# axiom_beta_plugin_module_1xPMOD.net
KiCad netlist of a schematic drawn in EAGLE
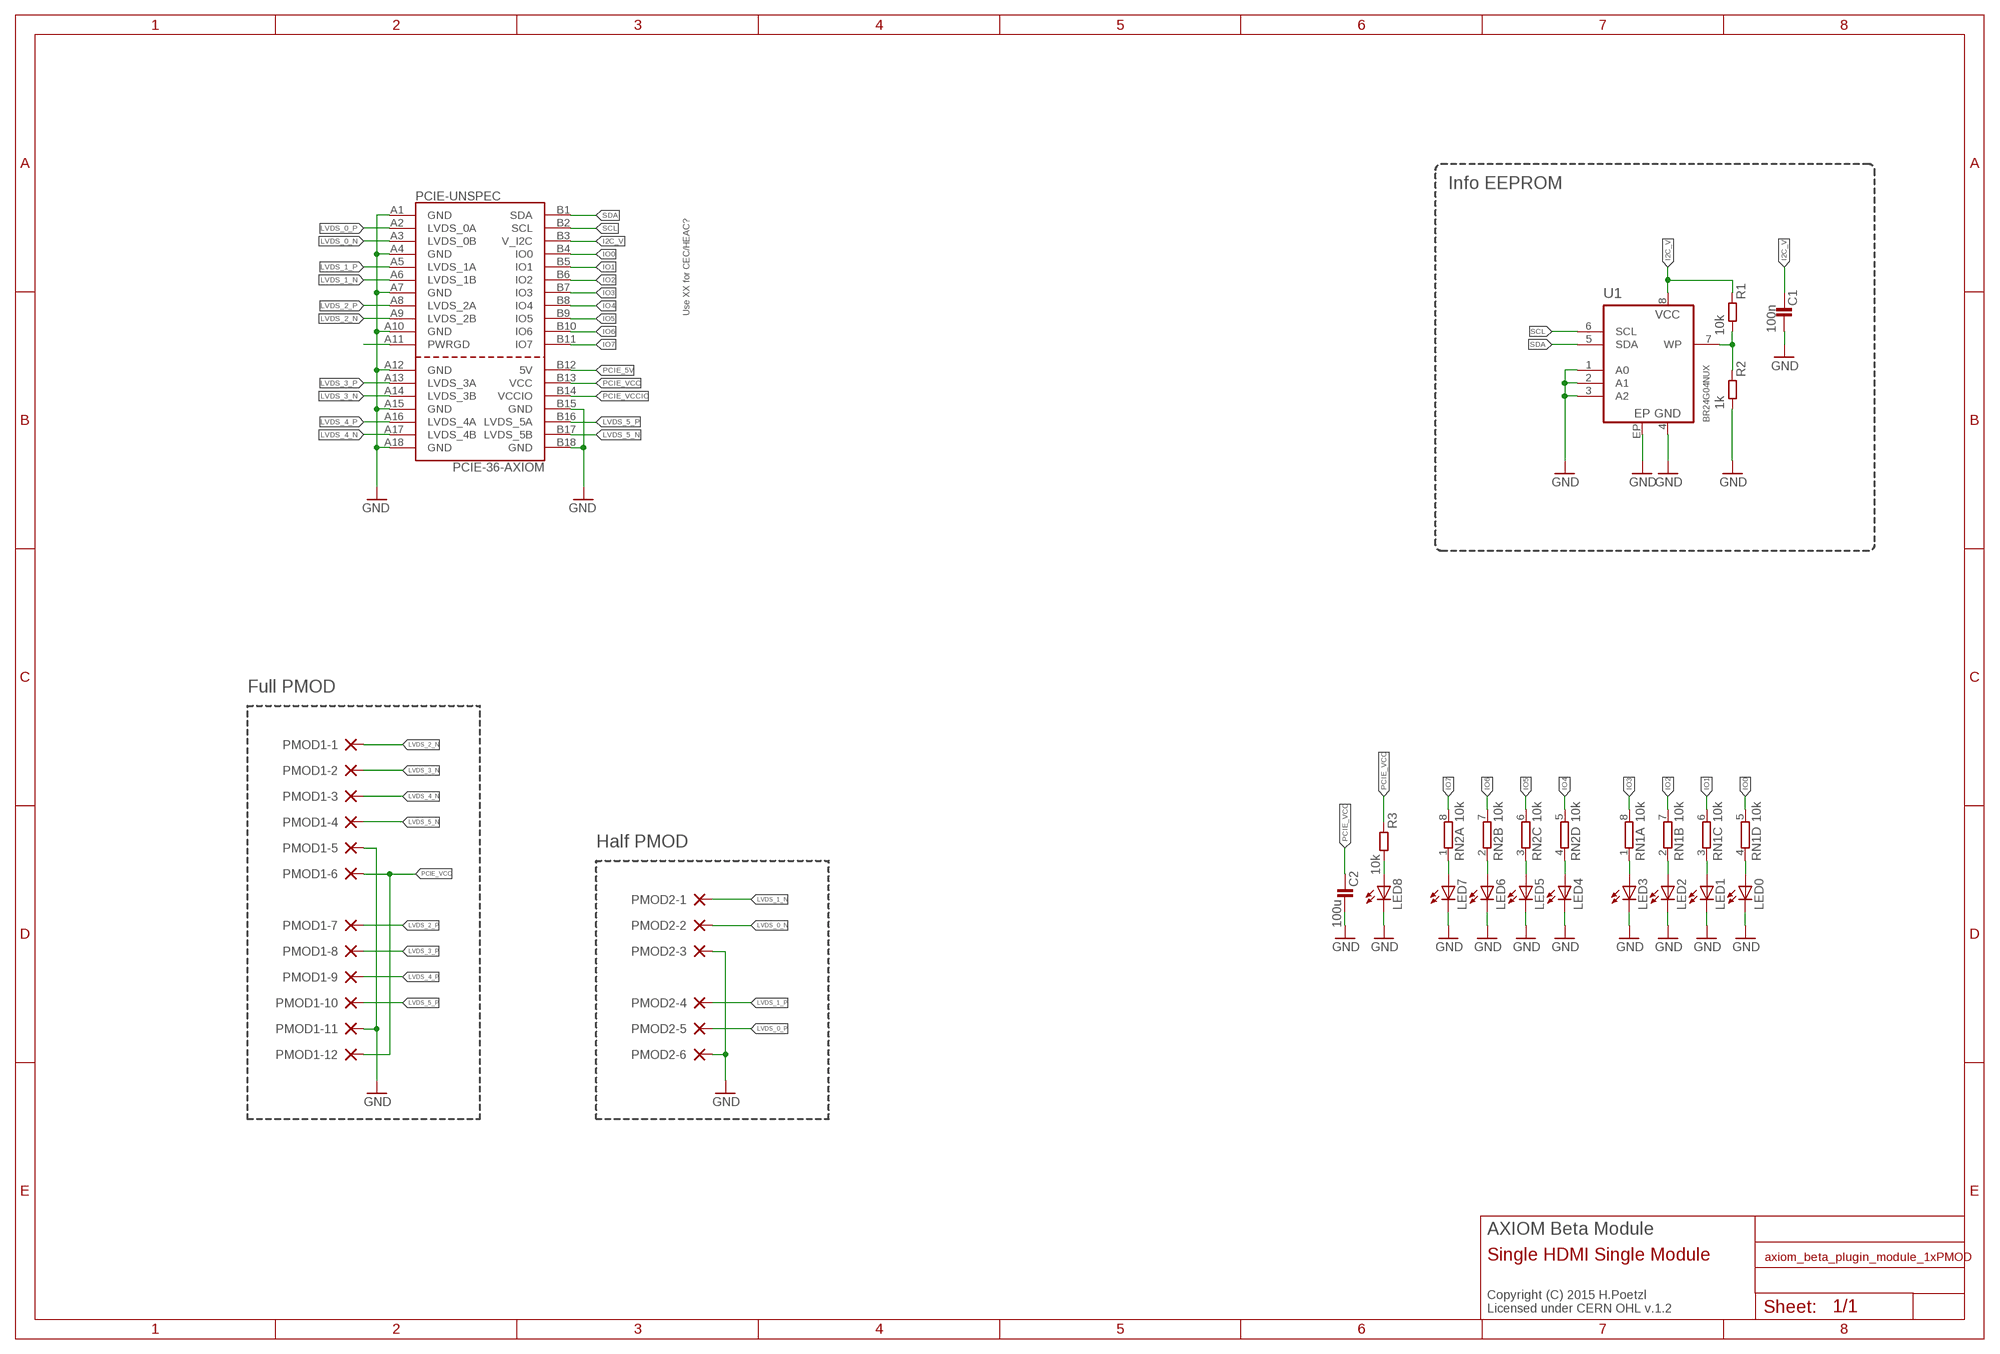
[diagram p0: schematic, sheet 1]

(export (version "E")
  (design (tool "Eeschema 10.0.6"))
  (components
    (comp (ref "C1")
      (value "100n")
      (footprint "eagle-import:0402-B")
      (libsource (lib "eagle-import") (part "C0402-B"))
    )
    (comp (ref "C2")
      (value "100u")
      (footprint "eagle-import:1206-A")
      (libsource (lib "eagle-import") (part "C1206-A"))
    )
    (comp (ref "LED0")
      (value "LEDCHIPLED_0603")
      (footprint "eagle-import:CHIPLED_0603")
      (libsource (lib "eagle-import") (part "LEDCHIPLED_0603"))
    )
    (comp (ref "LED1")
      (value "LEDCHIPLED_0603")
      (footprint "eagle-import:CHIPLED_0603")
      (libsource (lib "eagle-import") (part "LEDCHIPLED_0603"))
    )
    (comp (ref "LED2")
      (value "LEDCHIPLED_0603")
      (footprint "eagle-import:CHIPLED_0603")
      (libsource (lib "eagle-import") (part "LEDCHIPLED_0603"))
    )
    (comp (ref "LED3")
      (value "LEDCHIPLED_0603")
      (footprint "eagle-import:CHIPLED_0603")
      (libsource (lib "eagle-import") (part "LEDCHIPLED_0603"))
    )
    (comp (ref "LED4")
      (value "LEDCHIPLED_0603")
      (footprint "eagle-import:CHIPLED_0603")
      (libsource (lib "eagle-import") (part "LEDCHIPLED_0603"))
    )
    (comp (ref "LED5")
      (value "LEDCHIPLED_0603")
      (footprint "eagle-import:CHIPLED_0603")
      (libsource (lib "eagle-import") (part "LEDCHIPLED_0603"))
    )
    (comp (ref "LED6")
      (value "LEDCHIPLED_0603")
      (footprint "eagle-import:CHIPLED_0603")
      (libsource (lib "eagle-import") (part "LEDCHIPLED_0603"))
    )
    (comp (ref "LED7")
      (value "LEDCHIPLED_0603")
      (footprint "eagle-import:CHIPLED_0603")
      (libsource (lib "eagle-import") (part "LEDCHIPLED_0603"))
    )
    (comp (ref "LED8")
      (value "LEDCHIPLED_0603")
      (footprint "eagle-import:CHIPLED_0603")
      (libsource (lib "eagle-import") (part "LEDCHIPLED_0603"))
    )
    (comp (ref "PCIE-UNSPEC")
      (value "PCIE-36-AXIOM")
      (footprint "eagle-import:PCIE-36-AXIOM")
      (libsource (lib "eagle-import") (part "PCIE-36-AXIOM"))
    )
    (comp (ref "PMOD1-1")
      (value "SMD-PAD1.6X3.8MM-U")
      (footprint "eagle-import:1.6X3.8U-MM")
      (libsource (lib "eagle-import") (part "SMD-PAD1.6X3.8MM-U"))
    )
    (comp (ref "PMOD1-2")
      (value "SMD-PAD1.6X3.8MM-U")
      (footprint "eagle-import:1.6X3.8U-MM")
      (libsource (lib "eagle-import") (part "SMD-PAD1.6X3.8MM-U"))
    )
    (comp (ref "PMOD1-3")
      (value "SMD-PAD1.6X3.8MM-U")
      (footprint "eagle-import:1.6X3.8U-MM")
      (libsource (lib "eagle-import") (part "SMD-PAD1.6X3.8MM-U"))
    )
    (comp (ref "PMOD1-4")
      (value "SMD-PAD1.6X3.8MM-U")
      (footprint "eagle-import:1.6X3.8U-MM")
      (libsource (lib "eagle-import") (part "SMD-PAD1.6X3.8MM-U"))
    )
    (comp (ref "PMOD1-5")
      (value "SMD-PAD1.6X3.8MM-U")
      (footprint "eagle-import:1.6X3.8U-MM")
      (libsource (lib "eagle-import") (part "SMD-PAD1.6X3.8MM-U"))
    )
    (comp (ref "PMOD1-6")
      (value "SMD-PAD1.6X3.8MM-U")
      (footprint "eagle-import:1.6X3.8U-MM")
      (libsource (lib "eagle-import") (part "SMD-PAD1.6X3.8MM-U"))
    )
    (comp (ref "PMOD1-7")
      (value "SMD-PAD1.6X3.8MM-U")
      (footprint "eagle-import:1.6X3.8U-MM")
      (libsource (lib "eagle-import") (part "SMD-PAD1.6X3.8MM-U"))
    )
    (comp (ref "PMOD1-8")
      (value "SMD-PAD1.6X3.8MM-U")
      (footprint "eagle-import:1.6X3.8U-MM")
      (libsource (lib "eagle-import") (part "SMD-PAD1.6X3.8MM-U"))
    )
    (comp (ref "PMOD1-9")
      (value "SMD-PAD1.6X3.8MM-U")
      (footprint "eagle-import:1.6X3.8U-MM")
      (libsource (lib "eagle-import") (part "SMD-PAD1.6X3.8MM-U"))
    )
    (comp (ref "PMOD1-10")
      (value "SMD-PAD1.6X3.8MM-U")
      (footprint "eagle-import:1.6X3.8U-MM")
      (libsource (lib "eagle-import") (part "SMD-PAD1.6X3.8MM-U"))
    )
    (comp (ref "PMOD1-11")
      (value "SMD-PAD1.6X3.8MM-U")
      (footprint "eagle-import:1.6X3.8U-MM")
      (libsource (lib "eagle-import") (part "SMD-PAD1.6X3.8MM-U"))
    )
    (comp (ref "PMOD1-12")
      (value "SMD-PAD1.6X3.8MM-U")
      (footprint "eagle-import:1.6X3.8U-MM")
      (libsource (lib "eagle-import") (part "SMD-PAD1.6X3.8MM-U"))
    )
    (comp (ref "PMOD2-1")
      (value "SMD-PAD1.6X3.8MM-U")
      (footprint "eagle-import:1.6X3.8U-MM")
      (libsource (lib "eagle-import") (part "SMD-PAD1.6X3.8MM-U"))
    )
    (comp (ref "PMOD2-2")
      (value "SMD-PAD1.6X3.8MM-U")
      (footprint "eagle-import:1.6X3.8U-MM")
      (libsource (lib "eagle-import") (part "SMD-PAD1.6X3.8MM-U"))
    )
    (comp (ref "PMOD2-3")
      (value "SMD-PAD1.6X3.8MM-U")
      (footprint "eagle-import:1.6X3.8U-MM")
      (libsource (lib "eagle-import") (part "SMD-PAD1.6X3.8MM-U"))
    )
    (comp (ref "PMOD2-4")
      (value "SMD-PAD1.6X3.8MM-U")
      (footprint "eagle-import:1.6X3.8U-MM")
      (libsource (lib "eagle-import") (part "SMD-PAD1.6X3.8MM-U"))
    )
    (comp (ref "PMOD2-5")
      (value "SMD-PAD1.6X3.8MM-U")
      (footprint "eagle-import:1.6X3.8U-MM")
      (libsource (lib "eagle-import") (part "SMD-PAD1.6X3.8MM-U"))
    )
    (comp (ref "PMOD2-6")
      (value "SMD-PAD1.6X3.8MM-U")
      (footprint "eagle-import:1.6X3.8U-MM")
      (libsource (lib "eagle-import") (part "SMD-PAD1.6X3.8MM-U"))
    )
    (comp (ref "R1")
      (value "10k")
      (footprint "eagle-import:0402-B")
      (libsource (lib "eagle-import") (part "R0402-B"))
    )
    (comp (ref "R2")
      (value "1k")
      (footprint "eagle-import:0402-B")
      (libsource (lib "eagle-import") (part "R0402-B"))
    )
    (comp (ref "R3")
      (value "10k")
      (footprint "eagle-import:0402-B")
      (libsource (lib "eagle-import") (part "R0402-B"))
    )
    (comp (ref "RN1")
      (value "10k")
      (footprint "eagle-import:CAY16")
      (libsource (lib "eagle-import") (part "4R-NCAY16"))
    )
    (comp (ref "RN2")
      (value "10k")
      (footprint "eagle-import:CAY16")
      (libsource (lib "eagle-import") (part "4R-NCAY16"))
    )
    (comp (ref "U1")
      (value "BR24G04NUX")
      (footprint "eagle-import:DFN200X300X100-9N")
      (libsource (lib "eagle-import") (part "BR24G04NUX"))
    )
  )
  (nets
    (net (code "1") (name "GND") (class "Default")
      (node (ref "C1") (pin "2") (pinfunction "2_2") (pintype "passive"))
      (node (ref "C2") (pin "2") (pinfunction "2_2") (pintype "passive"))
      (node (ref "LED0") (pin "C") (pinfunction "C_C") (pintype "passive"))
      (node (ref "LED1") (pin "C") (pinfunction "C_C") (pintype "passive"))
      (node (ref "LED2") (pin "C") (pinfunction "C_C") (pintype "passive"))
      (node (ref "LED3") (pin "C") (pinfunction "C_C") (pintype "passive"))
      (node (ref "LED4") (pin "C") (pinfunction "C_C") (pintype "passive"))
      (node (ref "LED5") (pin "C") (pinfunction "C_C") (pintype "passive"))
      (node (ref "LED6") (pin "C") (pinfunction "C_C") (pintype "passive"))
      (node (ref "LED7") (pin "C") (pinfunction "C_C") (pintype "passive"))
      (node (ref "LED8") (pin "C") (pinfunction "C_C") (pintype "passive"))
      (node (ref "PCIE-UNSPEC") (pin "A1") (pinfunction "GND_A1") (pintype "passive"))
      (node (ref "PCIE-UNSPEC") (pin "A10") (pinfunction "GND_A10") (pintype "passive"))
      (node (ref "PCIE-UNSPEC") (pin "A12") (pinfunction "GND_A12") (pintype "passive"))
      (node (ref "PCIE-UNSPEC") (pin "A15") (pinfunction "GND_A15") (pintype "passive"))
      (node (ref "PCIE-UNSPEC") (pin "A18") (pinfunction "GND_A18") (pintype "passive"))
      (node (ref "PCIE-UNSPEC") (pin "A4") (pinfunction "GND_A4") (pintype "passive"))
      (node (ref "PCIE-UNSPEC") (pin "A7") (pinfunction "GND_A7") (pintype "passive"))
      (node (ref "PCIE-UNSPEC") (pin "B15") (pinfunction "GND_B15") (pintype "passive"))
      (node (ref "PCIE-UNSPEC") (pin "B18") (pinfunction "GND_B18") (pintype "passive"))
      (node (ref "PMOD1-11") (pin "1") (pinfunction "P_1") (pintype "passive"))
      (node (ref "PMOD1-5") (pin "1") (pinfunction "P_1") (pintype "passive"))
      (node (ref "PMOD2-3") (pin "1") (pinfunction "P_1") (pintype "passive"))
      (node (ref "PMOD2-6") (pin "1") (pinfunction "P_1") (pintype "passive"))
      (node (ref "R2") (pin "2") (pinfunction "2_2") (pintype "passive"))
      (node (ref "U1") (pin "1") (pinfunction "A0_1") (pintype "input"))
      (node (ref "U1") (pin "2") (pinfunction "A1_2") (pintype "input"))
      (node (ref "U1") (pin "3") (pinfunction "A2_3") (pintype "input"))
      (node (ref "U1") (pin "4") (pinfunction "GND_4") (pintype "passive"))
      (node (ref "U1") (pin "EP") (pinfunction "EP_EP") (pintype "passive"))
    )
    (net (code "2") (name "I2C_V") (class "Default")
      (node (ref "C1") (pin "1") (pinfunction "1_1") (pintype "passive"))
      (node (ref "PCIE-UNSPEC") (pin "B3") (pinfunction "V_I2C_B3") (pintype "passive"))
      (node (ref "R1") (pin "1") (pinfunction "1_1") (pintype "passive"))
      (node (ref "U1") (pin "8") (pinfunction "VCC_8") (pintype "power_in"))
    )
    (net (code "3") (name "IO0") (class "Default")
      (node (ref "PCIE-UNSPEC") (pin "B4") (pinfunction "IO0_B4") (pintype "passive"))
      (node (ref "RN1") (pin "5") (pinfunction "2_5") (pintype "passive"))
    )
    (net (code "4") (name "IO1") (class "Default")
      (node (ref "PCIE-UNSPEC") (pin "B5") (pinfunction "IO1_B5") (pintype "passive"))
      (node (ref "RN1") (pin "6") (pinfunction "2_6") (pintype "passive"))
    )
    (net (code "5") (name "IO2") (class "Default")
      (node (ref "PCIE-UNSPEC") (pin "B6") (pinfunction "IO2_B6") (pintype "passive"))
      (node (ref "RN1") (pin "7") (pinfunction "2_7") (pintype "passive"))
    )
    (net (code "6") (name "IO3") (class "Default")
      (node (ref "PCIE-UNSPEC") (pin "B7") (pinfunction "IO3_B7") (pintype "passive"))
      (node (ref "RN1") (pin "8") (pinfunction "2_8") (pintype "passive"))
    )
    (net (code "7") (name "IO4") (class "Default")
      (node (ref "PCIE-UNSPEC") (pin "B8") (pinfunction "IO4_B8") (pintype "passive"))
      (node (ref "RN2") (pin "5") (pinfunction "2_5") (pintype "passive"))
    )
    (net (code "8") (name "IO5") (class "Default")
      (node (ref "PCIE-UNSPEC") (pin "B9") (pinfunction "IO5_B9") (pintype "passive"))
      (node (ref "RN2") (pin "6") (pinfunction "2_6") (pintype "passive"))
    )
    (net (code "9") (name "IO6") (class "Default")
      (node (ref "PCIE-UNSPEC") (pin "B10") (pinfunction "IO6_B10") (pintype "passive"))
      (node (ref "RN2") (pin "7") (pinfunction "2_7") (pintype "passive"))
    )
    (net (code "10") (name "IO7") (class "Default")
      (node (ref "PCIE-UNSPEC") (pin "B11") (pinfunction "IO7_B11") (pintype "passive"))
      (node (ref "RN2") (pin "8") (pinfunction "2_8") (pintype "passive"))
    )
    (net (code "11") (name "LVDS_0_N") (class "Default")
      (node (ref "PCIE-UNSPEC") (pin "A3") (pinfunction "LVDS_0B_A3") (pintype "passive"))
      (node (ref "PMOD2-2") (pin "1") (pinfunction "P_1") (pintype "passive"))
    )
    (net (code "12") (name "LVDS_0_P") (class "Default")
      (node (ref "PCIE-UNSPEC") (pin "A2") (pinfunction "LVDS_0A_A2") (pintype "passive"))
      (node (ref "PMOD2-5") (pin "1") (pinfunction "P_1") (pintype "passive"))
    )
    (net (code "13") (name "LVDS_1_N") (class "Default")
      (node (ref "PCIE-UNSPEC") (pin "A6") (pinfunction "LVDS_1B_A6") (pintype "passive"))
      (node (ref "PMOD2-1") (pin "1") (pinfunction "P_1") (pintype "passive"))
    )
    (net (code "14") (name "LVDS_1_P") (class "Default")
      (node (ref "PCIE-UNSPEC") (pin "A5") (pinfunction "LVDS_1A_A5") (pintype "passive"))
      (node (ref "PMOD2-4") (pin "1") (pinfunction "P_1") (pintype "passive"))
    )
    (net (code "15") (name "LVDS_2_N") (class "Default")
      (node (ref "PCIE-UNSPEC") (pin "A9") (pinfunction "LVDS_2B_A9") (pintype "passive"))
      (node (ref "PMOD1-1") (pin "1") (pinfunction "P_1") (pintype "passive"))
    )
    (net (code "16") (name "LVDS_2_P") (class "Default")
      (node (ref "PCIE-UNSPEC") (pin "A8") (pinfunction "LVDS_2A_A8") (pintype "passive"))
      (node (ref "PMOD1-7") (pin "1") (pinfunction "P_1") (pintype "passive"))
    )
    (net (code "17") (name "LVDS_3_N") (class "Default")
      (node (ref "PCIE-UNSPEC") (pin "A14") (pinfunction "LVDS_3B_A14") (pintype "passive"))
      (node (ref "PMOD1-2") (pin "1") (pinfunction "P_1") (pintype "passive"))
    )
    (net (code "18") (name "LVDS_3_P") (class "Default")
      (node (ref "PCIE-UNSPEC") (pin "A13") (pinfunction "LVDS_3A_A13") (pintype "passive"))
      (node (ref "PMOD1-8") (pin "1") (pinfunction "P_1") (pintype "passive"))
    )
    (net (code "19") (name "LVDS_4_N") (class "Default")
      (node (ref "PCIE-UNSPEC") (pin "A17") (pinfunction "LVDS_4B_A17") (pintype "passive"))
      (node (ref "PMOD1-3") (pin "1") (pinfunction "P_1") (pintype "passive"))
    )
    (net (code "20") (name "LVDS_4_P") (class "Default")
      (node (ref "PCIE-UNSPEC") (pin "A16") (pinfunction "LVDS_4A_A16") (pintype "passive"))
      (node (ref "PMOD1-9") (pin "1") (pinfunction "P_1") (pintype "passive"))
    )
    (net (code "21") (name "LVDS_5_N") (class "Default")
      (node (ref "PCIE-UNSPEC") (pin "B17") (pinfunction "LVDS_5B_B17") (pintype "passive"))
      (node (ref "PMOD1-4") (pin "1") (pinfunction "P_1") (pintype "passive"))
    )
    (net (code "22") (name "LVDS_5_P") (class "Default")
      (node (ref "PCIE-UNSPEC") (pin "B16") (pinfunction "LVDS_5A_B16") (pintype "passive"))
      (node (ref "PMOD1-10") (pin "1") (pinfunction "P_1") (pintype "passive"))
    )
    (net (code "23") (name "Net-(LED3-PadA)") (class "Default")
      (node (ref "LED3") (pin "A") (pinfunction "A_A") (pintype "passive"))
      (node (ref "RN1") (pin "1") (pinfunction "1_1") (pintype "passive"))
    )
    (net (code "24") (name "Net-(LED7-PadA)") (class "Default")
      (node (ref "LED7") (pin "A") (pinfunction "A_A") (pintype "passive"))
      (node (ref "RN2") (pin "1") (pinfunction "1_1") (pintype "passive"))
    )
    (net (code "25") (name "Net-(LED8-PadA)") (class "Default")
      (node (ref "LED8") (pin "A") (pinfunction "A_A") (pintype "passive"))
      (node (ref "R3") (pin "2") (pinfunction "2_2") (pintype "passive"))
    )
    (net (code "26") (name "Net-(RN1B-1)") (class "Default")
      (node (ref "LED2") (pin "A") (pinfunction "A_A") (pintype "passive"))
      (node (ref "RN1") (pin "2") (pinfunction "1_2") (pintype "passive"))
    )
    (net (code "27") (name "Net-(RN1C-1)") (class "Default")
      (node (ref "LED1") (pin "A") (pinfunction "A_A") (pintype "passive"))
      (node (ref "RN1") (pin "3") (pinfunction "1_3") (pintype "passive"))
    )
    (net (code "28") (name "Net-(RN1D-1)") (class "Default")
      (node (ref "LED0") (pin "A") (pinfunction "A_A") (pintype "passive"))
      (node (ref "RN1") (pin "4") (pinfunction "1_4") (pintype "passive"))
    )
    (net (code "29") (name "Net-(RN2B-1)") (class "Default")
      (node (ref "LED6") (pin "A") (pinfunction "A_A") (pintype "passive"))
      (node (ref "RN2") (pin "2") (pinfunction "1_2") (pintype "passive"))
    )
    (net (code "30") (name "Net-(RN2C-1)") (class "Default")
      (node (ref "LED5") (pin "A") (pinfunction "A_A") (pintype "passive"))
      (node (ref "RN2") (pin "3") (pinfunction "1_3") (pintype "passive"))
    )
    (net (code "31") (name "Net-(RN2D-1)") (class "Default")
      (node (ref "LED4") (pin "A") (pinfunction "A_A") (pintype "passive"))
      (node (ref "RN2") (pin "4") (pinfunction "1_4") (pintype "passive"))
    )
    (net (code "32") (name "Net-(U1-WP)") (class "Default")
      (node (ref "R1") (pin "2") (pinfunction "2_2") (pintype "passive"))
      (node (ref "R2") (pin "1") (pinfunction "1_1") (pintype "passive"))
      (node (ref "U1") (pin "7") (pinfunction "WP_7") (pintype "input"))
    )
    (net (code "33") (name "PCIE_5V") (class "Default")
      (node (ref "PCIE-UNSPEC") (pin "B12") (pinfunction "5V_B12") (pintype "passive"))
    )
    (net (code "34") (name "PCIE_VCC") (class "Default")
      (node (ref "C2") (pin "1") (pinfunction "1_1") (pintype "passive"))
      (node (ref "PCIE-UNSPEC") (pin "B13") (pinfunction "VCC_B13") (pintype "passive"))
      (node (ref "PMOD1-12") (pin "1") (pinfunction "P_1") (pintype "passive"))
      (node (ref "PMOD1-6") (pin "1") (pinfunction "P_1") (pintype "passive"))
      (node (ref "R3") (pin "1") (pinfunction "1_1") (pintype "passive"))
    )
    (net (code "35") (name "PCIE_VCCIO") (class "Default")
      (node (ref "PCIE-UNSPEC") (pin "B14") (pinfunction "VCCIO_B14") (pintype "passive"))
    )
    (net (code "36") (name "SCL") (class "Default")
      (node (ref "PCIE-UNSPEC") (pin "B2") (pinfunction "SCL_B2") (pintype "passive"))
      (node (ref "U1") (pin "6") (pinfunction "SCL_6") (pintype "input"))
    )
    (net (code "37") (name "SDA") (class "Default")
      (node (ref "PCIE-UNSPEC") (pin "B1") (pinfunction "SDA_B1") (pintype "passive"))
      (node (ref "U1") (pin "5") (pinfunction "SDA_5") (pintype "bidirectional"))
    )
    (net (code "38") (name "unconnected-(PCIE-UNSPEC-PWRGD-PadA11)") (class "Default")
      (node (ref "PCIE-UNSPEC") (pin "A11") (pinfunction "PWRGD_A11") (pintype "passive"))
    )
  )
)
